# power_supply.net
KiCad netlist of a schematic drawn in Altium Designer
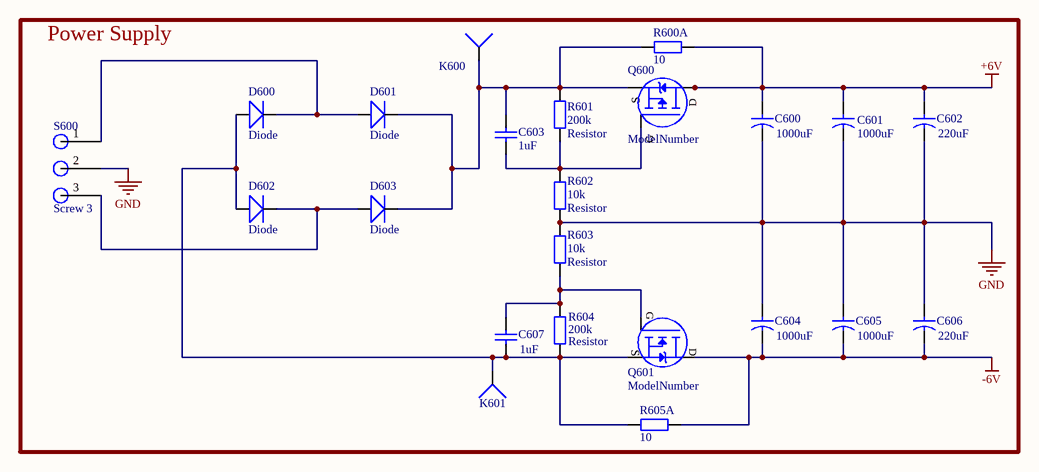
[diagram p0: power_supply.SchDoc]

(export (version "E")
  (design (tool "Eeschema 10.0.6"))
  (components
    (comp (ref "C600")
      (value "1000uF")
      (footprint "Cap Lyt Ø18")
      (fields (field (name "Comment") "Cap"))
      (libsource (lib "AAURacing") (part "Capacitor electrolytic"))
    )
    (comp (ref "C601")
      (value "1000uF")
      (footprint "Cap Lyt Ø18")
      (fields (field (name "Comment") "Cap"))
      (libsource (lib "AAURacing") (part "Capacitor electrolytic"))
    )
    (comp (ref "C602")
      (value "220uF")
      (footprint "Cap Lyt Ø8")
      (fields (field (name "Comment") "Cap"))
      (libsource (lib "AAURacing") (part "Capacitor electrolytic"))
    )
    (comp (ref "C603")
      (value "1uF")
      (footprint "Cap-1")
      (fields (field (name "Comment") "Cap"))
      (libsource (lib "AAURacing") (part "Capacitor 1 space"))
    )
    (comp (ref "C604")
      (value "1000uF")
      (footprint "Cap Lyt Ø18")
      (fields (field (name "Comment") "Cap"))
      (libsource (lib "AAURacing") (part "Capacitor electrolytic"))
    )
    (comp (ref "C605")
      (value "1000uF")
      (footprint "Cap Lyt Ø18")
      (fields (field (name "Comment") "Cap"))
      (libsource (lib "AAURacing") (part "Capacitor electrolytic"))
    )
    (comp (ref "C606")
      (value "220uF")
      (footprint "Cap Lyt Ø8")
      (fields (field (name "Comment") "Cap"))
      (libsource (lib "AAURacing") (part "Capacitor electrolytic"))
    )
    (comp (ref "C607")
      (value "1uF")
      (footprint "Cap-1")
      (fields (field (name "Comment") "Cap"))
      (libsource (lib "AAURacing") (part "Capacitor 1 space"))
    )
    (comp (ref "D600")
      (value "Diode")
      (footprint "Diode 1A")
      (libsource (lib "mit_seje_library") (part "Diode"))
    )
    (comp (ref "D601")
      (value "Diode")
      (footprint "Diode 1A")
      (libsource (lib "mit_seje_library") (part "Diode"))
    )
    (comp (ref "D602")
      (value "Diode")
      (footprint "Diode 1A")
      (libsource (lib "mit_seje_library") (part "Diode"))
    )
    (comp (ref "D603")
      (value "Diode")
      (footprint "Diode 1A")
      (libsource (lib "mit_seje_library") (part "Diode"))
    )
    (comp (ref "K600") (value "Wire") (footprint "Wire 1.5mm") (libsource (lib "AAURacing") (part "Wire")))
    (comp (ref "K601") (value "Wire") (footprint "Wire 1.5mm") (libsource (lib "AAURacing") (part "Wire")))
    (comp (ref "Q600")
      (value "ModelNum")
      (footprint "TO-220")
      (fields (field (name "MODEL") "ModelNumber"))
      (libsource (lib "AAURacing") (part "MOSFET P-Channel"))
    )
    (comp (ref "Q601")
      (value "ModelNum")
      (footprint "TO-220")
      (fields (field (name "MODEL") "ModelNumber"))
      (libsource (lib "AAURacing") (part "MOSFET N-Channel"))
    )
    (comp (ref "R600")
      (value "10")
      (footprint "POW RES THT 13mm")
      (libsource (lib "mit_seje_library") (part "POW RES THT 13mm"))
    )
    (comp (ref "R601")
      (value "Resistor")
      (footprint "RES THT 9mm")
      (fields (field (name "ALTIUM_VALUE") "200k"))
      (libsource (lib "AAURacing") (part "Resistor"))
    )
    (comp (ref "R602")
      (value "Resistor")
      (footprint "RES THT 9mm")
      (fields (field (name "ALTIUM_VALUE") "10k"))
      (libsource (lib "AAURacing") (part "Resistor"))
    )
    (comp (ref "R603")
      (value "Resistor")
      (footprint "RES THT 9mm")
      (fields (field (name "ALTIUM_VALUE") "10k"))
      (libsource (lib "AAURacing") (part "Resistor"))
    )
    (comp (ref "R604")
      (value "Resistor")
      (footprint "RES THT 9mm")
      (fields (field (name "ALTIUM_VALUE") "200k"))
      (libsource (lib "AAURacing") (part "Resistor"))
    )
    (comp (ref "R605")
      (value "10")
      (footprint "POW RES THT 13mm")
      (libsource (lib "mit_seje_library") (part "POW RES THT 13mm"))
    )
    (comp (ref "S600") (value "Screw 3") (footprint "Screw-3") (libsource (lib "AAURacing") (part "Screw 3")))
  )
  (nets
    (net (code "1") (name "+6V") (class "Default")
      (node (ref "C600") (pin "1") (pinfunction "1_1") (pintype "passive"))
      (node (ref "C601") (pin "1") (pinfunction "1_1") (pintype "passive"))
      (node (ref "C602") (pin "1") (pinfunction "1_1") (pintype "passive"))
      (node (ref "Q600") (pin "3") (pinfunction "D_3") (pintype "passive"))
      (node (ref "Q600") (pin "4") (pinfunction "D_4") (pintype "passive"))
      (node (ref "R600") (pin "2") (pinfunction "2_2") (pintype "passive"))
    )
    (net (code "2") (name "-6V") (class "Default")
      (node (ref "C604") (pin "2") (pinfunction "g_2") (pintype "passive"))
      (node (ref "C605") (pin "2") (pinfunction "g_2") (pintype "passive"))
      (node (ref "C606") (pin "2") (pinfunction "g_2") (pintype "passive"))
      (node (ref "Q601") (pin "2") (pinfunction "D_2") (pintype "passive"))
      (node (ref "R605") (pin "2") (pinfunction "2_2") (pintype "passive"))
    )
    (net (code "3") (name "GND") (class "Default")
      (node (ref "C600") (pin "2") (pinfunction "g_2") (pintype "passive"))
      (node (ref "C601") (pin "2") (pinfunction "g_2") (pintype "passive"))
      (node (ref "C602") (pin "2") (pinfunction "g_2") (pintype "passive"))
      (node (ref "C604") (pin "1") (pinfunction "1_1") (pintype "passive"))
      (node (ref "C605") (pin "1") (pinfunction "1_1") (pintype "passive"))
      (node (ref "C606") (pin "1") (pinfunction "1_1") (pintype "passive"))
      (node (ref "R602") (pin "1") (pinfunction "1_1") (pintype "passive"))
      (node (ref "R603") (pin "2") (pinfunction "2_2") (pintype "passive"))
      (node (ref "S600") (pin "2") (pinfunction "2_2") (pintype "passive"))
    )
    (net (code "4") (name "Net-(C603-g)") (class "Default")
      (node (ref "C603") (pin "2") (pinfunction "g_2") (pintype "passive"))
      (node (ref "D601") (pin "2") (pinfunction "2_2") (pintype "passive"))
      (node (ref "D603") (pin "2") (pinfunction "2_2") (pintype "passive"))
      (node (ref "K600") (pin "1") (pinfunction "1_1") (pintype "passive"))
      (node (ref "Q600") (pin "1") (pinfunction "S_1") (pintype "passive"))
      (node (ref "R600") (pin "1") (pinfunction "1_1") (pintype "passive"))
      (node (ref "R601") (pin "2") (pinfunction "2_2") (pintype "passive"))
    )
    (net (code "5") (name "Net-(C607-g)") (class "Default")
      (node (ref "C607") (pin "2") (pinfunction "g_2") (pintype "passive"))
      (node (ref "Q601") (pin "1") (pinfunction "G_1") (pintype "passive"))
      (node (ref "R603") (pin "1") (pinfunction "1_1") (pintype "passive"))
      (node (ref "R604") (pin "2") (pinfunction "2_2") (pintype "passive"))
    )
    (net (code "6") (name "Net-(D600-Pad2)") (class "Default")
      (node (ref "D600") (pin "2") (pinfunction "2_2") (pintype "passive"))
      (node (ref "D601") (pin "1") (pinfunction "1_1") (pintype "passive"))
      (node (ref "S600") (pin "1") (pinfunction "1_1") (pintype "passive"))
    )
    (net (code "7") (name "Net-(D602-Pad2)") (class "Default")
      (node (ref "D602") (pin "2") (pinfunction "2_2") (pintype "passive"))
      (node (ref "D603") (pin "1") (pinfunction "1_1") (pintype "passive"))
      (node (ref "S600") (pin "3") (pinfunction "3_3") (pintype "passive"))
    )
    (net (code "8") (name "Net-(Q600-G)") (class "Default")
      (node (ref "C603") (pin "1") (pinfunction "1_1") (pintype "passive"))
      (node (ref "Q600") (pin "2") (pinfunction "G_2") (pintype "passive"))
      (node (ref "R601") (pin "1") (pinfunction "1_1") (pintype "passive"))
      (node (ref "R602") (pin "2") (pinfunction "2_2") (pintype "passive"))
    )
    (net (code "9") (name "Net-(Q601-S)") (class "Default")
      (node (ref "C607") (pin "1") (pinfunction "1_1") (pintype "passive"))
      (node (ref "D600") (pin "1") (pinfunction "1_1") (pintype "passive"))
      (node (ref "D602") (pin "1") (pinfunction "1_1") (pintype "passive"))
      (node (ref "K601") (pin "1") (pinfunction "1_1") (pintype "passive"))
      (node (ref "Q601") (pin "3") (pinfunction "S_3") (pintype "passive"))
      (node (ref "R604") (pin "1") (pinfunction "1_1") (pintype "passive"))
      (node (ref "R605") (pin "1") (pinfunction "1_1") (pintype "passive"))
    )
  )
)
